# main.net
KiCad netlist of a schematic drawn in Altium Designer
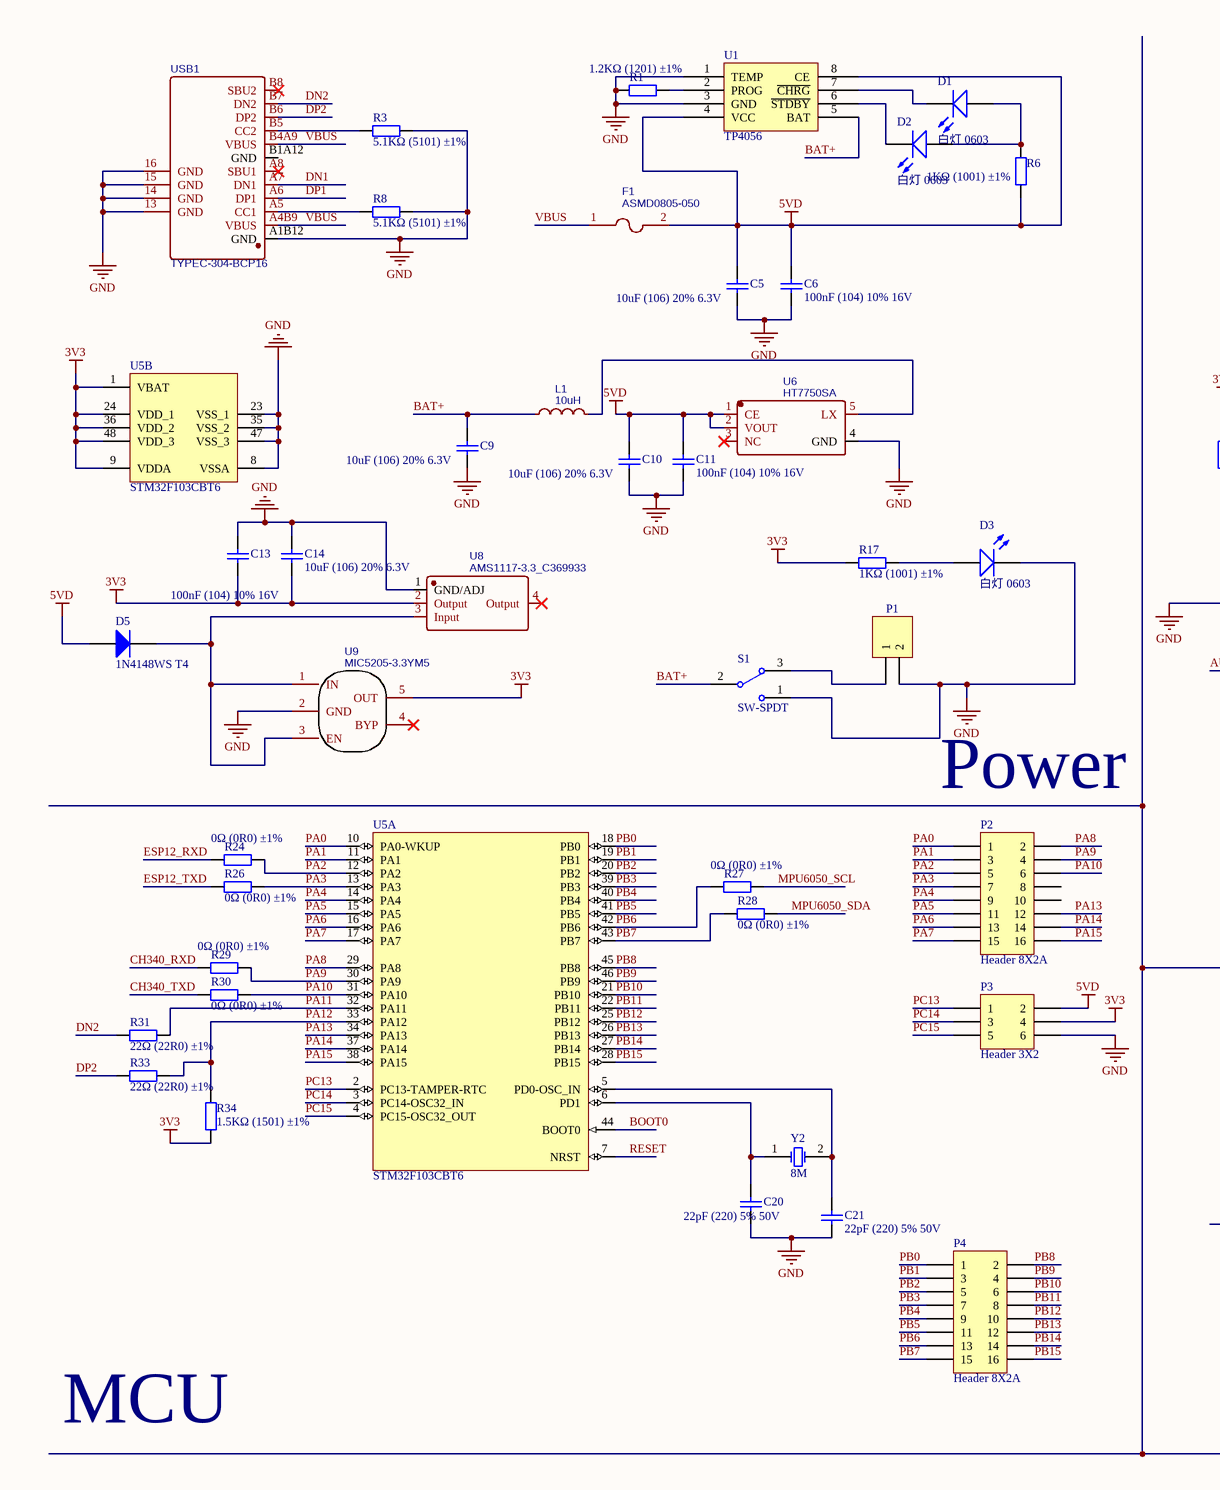
[diagram p0: main.SchDoc, left]
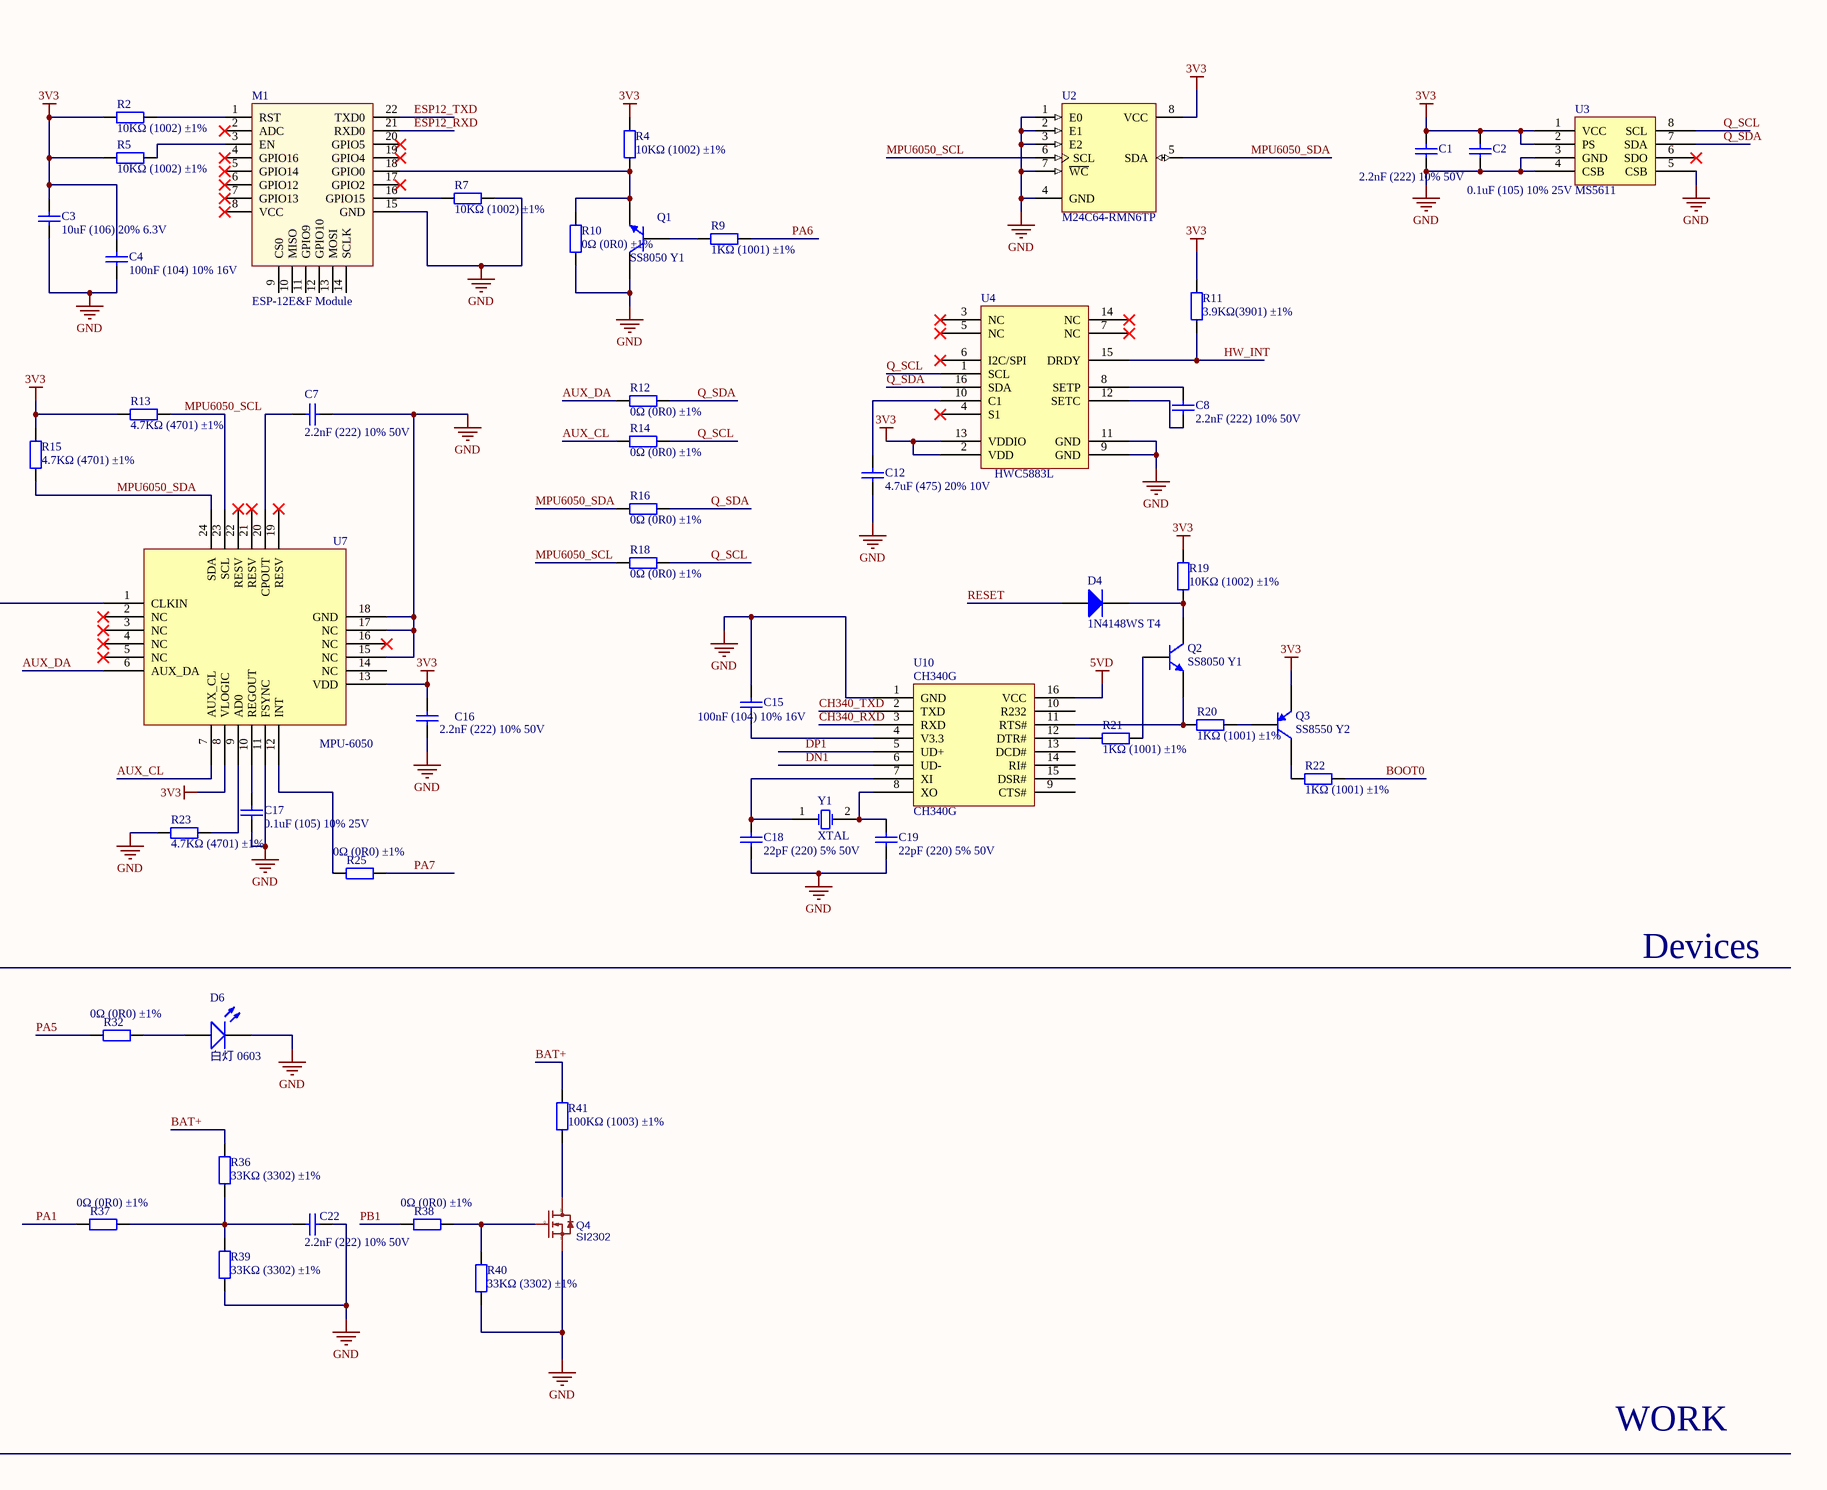
[diagram p1: main.SchDoc, right]

(export (version "E")
  (design (tool "Eeschema 10.0.6"))
  (components
    (comp (ref "C1")
      (value "2.2nF (222) 10% 50V")
      (footprint "0402_C")
      (description "贴片电容")
      (libsource (lib "Miscellaneous Devices LC") (part "0402 2.2nF (222) 10% 50V"))
    )
    (comp (ref "C2")
      (value "0.1uF (105) 10% 25V")
      (footprint "0402_C")
      (description "贴片电容")
      (libsource (lib "Miscellaneous Devices LC") (part "0402 1.0uF (105) 10% 25V"))
    )
    (comp (ref "C3")
      (value "10uF (106) 20% 6.3V")
      (footprint "0402_C")
      (description "贴片电容")
      (libsource (lib "Miscellaneous Devices LC") (part "0402 10uF (106) 20% 6.3V"))
    )
    (comp (ref "C4")
      (value "100nF (104) 10% 16V")
      (footprint "0402_C")
      (description "贴片电容")
      (libsource (lib "Miscellaneous Devices LC") (part "0402 100nF (104) 10% 16V"))
    )
    (comp (ref "C5")
      (value "10uF (106) 20% 6.3V")
      (footprint "0402_C")
      (description "贴片电容")
      (libsource (lib "Miscellaneous Devices LC") (part "0402 10uF (106) 20% 6.3V"))
    )
    (comp (ref "C6")
      (value "100nF (104) 10% 16V")
      (footprint "0402_C")
      (description "贴片电容")
      (libsource (lib "Miscellaneous Devices LC") (part "0402 100nF (104) 10% 16V"))
    )
    (comp (ref "C7")
      (value "2.2nF (222) 10% 50V")
      (footprint "0402_C")
      (description "贴片电容")
      (libsource (lib "Miscellaneous Devices LC") (part "0402 2.2nF (222) 10% 50V"))
    )
    (comp (ref "C8")
      (value "2.2nF (222) 10% 50V")
      (footprint "0402_C")
      (description "贴片电容")
      (libsource (lib "Miscellaneous Devices LC") (part "0402 2.2nF (222) 10% 50V"))
    )
    (comp (ref "C9")
      (value "10uF (106) 20% 6.3V")
      (footprint "0402_C")
      (description "贴片电容")
      (libsource (lib "Miscellaneous Devices LC") (part "0402 10uF (106) 20% 6.3V"))
    )
    (comp (ref "C10")
      (value "10uF (106) 20% 6.3V")
      (footprint "0402_C")
      (description "贴片电容")
      (libsource (lib "Miscellaneous Devices LC") (part "0402 10uF (106) 20% 6.3V"))
    )
    (comp (ref "C11")
      (value "100nF (104) 10% 16V")
      (footprint "0402_C")
      (description "贴片电容")
      (libsource (lib "Miscellaneous Devices LC") (part "0402 100nF (104) 10% 16V"))
    )
    (comp (ref "C12")
      (value "4.7uF (475) 20% 10V")
      (footprint "0402_C")
      (description "贴片电容")
      (libsource (lib "Miscellaneous Devices LC") (part "0402 4.7uF (475) 20% 10V"))
    )
    (comp (ref "C13")
      (value "100nF (104) 10% 16V")
      (footprint "0402_C")
      (description "贴片电容")
      (libsource (lib "Miscellaneous Devices LC") (part "0402 100nF (104) 10% 16V"))
    )
    (comp (ref "C14")
      (value "10uF (106) 20% 6.3V")
      (footprint "0402_C")
      (description "贴片电容")
      (libsource (lib "Miscellaneous Devices LC") (part "0402 10uF (106) 20% 6.3V"))
    )
    (comp (ref "C15")
      (value "100nF (104) 10% 16V")
      (footprint "0402_C")
      (description "贴片电容")
      (libsource (lib "Miscellaneous Devices LC") (part "0402 100nF (104) 10% 16V"))
    )
    (comp (ref "C16")
      (value "2.2nF (222) 10% 50V")
      (footprint "0402_C")
      (description "贴片电容")
      (libsource (lib "Miscellaneous Devices LC") (part "0402 2.2nF (222) 10% 50V"))
    )
    (comp (ref "C17")
      (value "0.1uF (105) 10% 25V")
      (footprint "0402_C")
      (description "贴片电容")
      (libsource (lib "Miscellaneous Devices LC") (part "0402 1.0uF (105) 10% 25V"))
    )
    (comp (ref "C18")
      (value "22pF (220) 5% 50V")
      (footprint "0402_C")
      (description "贴片电容")
      (libsource (lib "Miscellaneous Devices LC") (part "0402 22pF (220) 5% 50V"))
    )
    (comp (ref "C19")
      (value "22pF (220) 5% 50V")
      (footprint "0402_C")
      (description "贴片电容")
      (libsource (lib "Miscellaneous Devices LC") (part "0402 22pF (220) 5% 50V"))
    )
    (comp (ref "C20")
      (value "22pF (220) 5% 50V")
      (footprint "0402_C")
      (description "贴片电容")
      (libsource (lib "Miscellaneous Devices LC") (part "0402 22pF (220) 5% 50V"))
    )
    (comp (ref "C21")
      (value "22pF (220) 5% 50V")
      (footprint "0402_C")
      (description "贴片电容")
      (libsource (lib "Miscellaneous Devices LC") (part "0402 22pF (220) 5% 50V"))
    )
    (comp (ref "C22")
      (value "2.2nF (222) 10% 50V")
      (footprint "0402_C")
      (description "贴片电容")
      (libsource (lib "Miscellaneous Devices LC") (part "0402 2.2nF (222) 10% 50V"))
    )
    (comp (ref "D1")
      (value "白灯 0603")
      (footprint "0603_LED_S1")
      (description "发光二极管")
      (libsource (lib "Miscellaneous Devices LC") (part "0603 白灯"))
    )
    (comp (ref "D2")
      (value "白灯 0603")
      (footprint "0603_LED_S1")
      (description "发光二极管")
      (libsource (lib "Miscellaneous Devices LC") (part "0603 白灯"))
    )
    (comp (ref "D3")
      (value "白灯 0603")
      (footprint "0603_LED_S1")
      (description "发光二极管")
      (libsource (lib "Miscellaneous Devices LC") (part "0603 白灯"))
    )
    (comp (ref "D4")
      (value "1N4148WS T4")
      (footprint "SOD-323_L1.8-W1.3-LS2.5-RD")
      (description "二极管")
      (libsource (lib "Miscellaneous Devices LC") (part "SOD-323 1N4148WS T4"))
    )
    (comp (ref "D5")
      (value "1N4148WS T4")
      (footprint "SOD-323_L1.8-W1.3-LS2.5-RD")
      (description "二极管")
      (libsource (lib "Miscellaneous Devices LC") (part "SOD-323 1N4148WS T4"))
    )
    (comp (ref "D6")
      (value "白灯 0603")
      (footprint "0603_LED_S1")
      (description "发光二极管")
      (libsource (lib "Miscellaneous Devices LC") (part "0603 白灯"))
    )
    (comp (ref "F1")
      (value "ASMD0805-050")
      (footprint "F0805")
      (fields (field (name "BOM_SUPPLIER PART") "C135329") (field (name "CONTRIBUTOR") "LCSC"))
      (libsource (lib "altium-import") (part "root_0_ASMD0805-050_"))
    )
    (comp (ref "L1")
      (value "10uH")
      (footprint "IND-SMD_L3.0-W3.0_SWPA3010S")
      (fields
        (field (name "BOM_MANUFACTURER PART") "SWPA3012S100MT")
        (field (name "BOM_SUPPLIER PART") "C48668")
      )
      (libsource (lib "altium-import") (part "root_0_10uH_"))
    )
    (comp (ref "M1")
      (value "ESP-12E&F Module")
      (footprint "ESP-12E&F Module")
      (libsource (lib "smartclock") (part "ESP-12E&F Module"))
    )
    (comp (ref "P1")
      (value "Header 2")
      (footprint "HDR2X1_A")
      (description "接插件")
      (fields (field (name "PUBLISHER") "Altium Limited"))
      (libsource (lib "Fszhang") (part "Header 2"))
    )
    (comp (ref "P2")
      (value "Header 8X2A")
      (footprint "HDR8X2_A1")
      (description "接插件")
      (fields (field (name "PUBLISHER") "Altium Limited"))
      (libsource (lib "Fszhang") (part "Header 8X2A"))
    )
    (comp (ref "P3")
      (value "Header 3X2")
      (footprint "HDR2X3")
      (description "Header, 3-Pin, Dual row")
      (fields (field (name "PUBLISHER") "Altium Limited"))
      (libsource (lib "Sparks") (part "Header 3X2"))
    )
    (comp (ref "P4")
      (value "Header 8X2A")
      (footprint "HDR8X2_A1")
      (description "接插件")
      (fields (field (name "PUBLISHER") "Altium Limited"))
      (libsource (lib "Fszhang") (part "Header 8X2A"))
    )
    (comp (ref "Q1")
      (value "SS8050 Y1")
      (footprint "SOT-23(SOT-23-3)")
      (description "三极管")
      (libsource (lib "Miscellaneous Devices LC") (part "SOT-23 SS8050 Y1"))
    )
    (comp (ref "Q2")
      (value "SS8050 Y1")
      (footprint "SOT-23(SOT-23-3)")
      (description "三极管")
      (libsource (lib "Miscellaneous Devices LC") (part "SOT-23 SS8050 Y1"))
    )
    (comp (ref "Q3")
      (value "SS8550 Y2")
      (footprint "SOT-23(SOT-23-3)")
      (description "三极管")
      (libsource (lib "Miscellaneous Devices LC") (part "SOT-23 SS8550 Y2"))
    )
    (comp (ref "Q4")
      (value "SI2302")
      (footprint "SOT-23-3_L2.9-W1.3-P1.90-LS2.4-BR")
      (fields (field (name "BOM_SUPPLIER PART") "C181087") (field (name "CONTRIBUTOR") "LCSC"))
      (libsource (lib "altium-import") (part "root_0_SI2302_"))
    )
    (comp (ref "R1")
      (value "1.2KΩ (1201) ±1%")
      (footprint "0402_R")
      (description "贴片电阻")
      (libsource (lib "Miscellaneous Devices LC") (part "0402 1.2KΩ (1201) 1%"))
    )
    (comp (ref "R2")
      (value "10KΩ (1002) ±1%")
      (footprint "0402_R")
      (description "贴片电阻")
      (libsource (lib "Miscellaneous Devices LC") (part "0402 10KΩ (1002) 1%"))
    )
    (comp (ref "R3")
      (value "5.1KΩ (5101) ±1%")
      (footprint "0402_R")
      (description "贴片电阻")
      (libsource (lib "Miscellaneous Devices LC") (part "0402 5.1KΩ (5101) 1%"))
    )
    (comp (ref "R4")
      (value "10KΩ (1002) ±1%")
      (footprint "0402_R")
      (description "贴片电阻")
      (libsource (lib "") (part "0402 10KΩ (1002) 1%_1"))
    )
    (comp (ref "R5")
      (value "10KΩ (1002) ±1%")
      (footprint "0402_R")
      (description "贴片电阻")
      (libsource (lib "Miscellaneous Devices LC") (part "0402 10KΩ (1002) 1%"))
    )
    (comp (ref "R6")
      (value "1KΩ (1001) ±1%")
      (footprint "0402_R")
      (description "贴片电阻")
      (libsource (lib "") (part "0402 1KΩ (1001) 1%_2"))
    )
    (comp (ref "R7")
      (value "10KΩ (1002) ±1%")
      (footprint "0402_R")
      (description "贴片电阻")
      (libsource (lib "Miscellaneous Devices LC") (part "0402 10KΩ (1002) 1%"))
    )
    (comp (ref "R8")
      (value "5.1KΩ (5101) ±1%")
      (footprint "0402_R")
      (description "贴片电阻")
      (libsource (lib "Miscellaneous Devices LC") (part "0402 5.1KΩ (5101) 1%"))
    )
    (comp (ref "R9")
      (value "1KΩ (1001) ±1%")
      (footprint "0402_R")
      (description "贴片电阻")
      (libsource (lib "Miscellaneous Devices LC") (part "0402 1KΩ (1001) 1%"))
    )
    (comp (ref "R10")
      (value "0Ω (0R0) ±1%")
      (footprint "0402_R")
      (description "贴片电阻")
      (libsource (lib "") (part "0402 0Ω (0R0) 1%_1"))
    )
    (comp (ref "R11")
      (value "3.9KΩ(3901) ±1%")
      (footprint "0402_R")
      (description "贴片电阻")
      (libsource (lib "Miscellaneous Devices LC") (part "0402 3.9KΩ(3901) 1%"))
    )
    (comp (ref "R12")
      (value "0Ω (0R0) ±1%")
      (footprint "0402_R")
      (description "贴片电阻")
      (libsource (lib "Miscellaneous Devices LC") (part "0402 0Ω (0R0) 1%"))
    )
    (comp (ref "R13")
      (value "4.7KΩ (4701) ±1%")
      (footprint "0402_R")
      (description "贴片电阻")
      (libsource (lib "Miscellaneous Devices LC") (part "0402 4.7KΩ (4701) 1%"))
    )
    (comp (ref "R14")
      (value "0Ω (0R0) ±1%")
      (footprint "0402_R")
      (description "贴片电阻")
      (libsource (lib "Miscellaneous Devices LC") (part "0402 0Ω (0R0) 1%"))
    )
    (comp (ref "R15")
      (value "4.7KΩ (4701) ±1%")
      (footprint "0402_R")
      (description "贴片电阻")
      (libsource (lib "") (part "0402 4.7KΩ (4701) 1%_2"))
    )
    (comp (ref "R16")
      (value "0Ω (0R0) ±1%")
      (footprint "0402_R")
      (description "贴片电阻")
      (libsource (lib "Miscellaneous Devices LC") (part "0402 0Ω (0R0) 1%"))
    )
    (comp (ref "R17")
      (value "1KΩ (1001) ±1%")
      (footprint "0402_R")
      (description "贴片电阻")
      (libsource (lib "Miscellaneous Devices LC") (part "0402 1KΩ (1001) 1%"))
    )
    (comp (ref "R18")
      (value "0Ω (0R0) ±1%")
      (footprint "0402_R")
      (description "贴片电阻")
      (libsource (lib "Miscellaneous Devices LC") (part "0402 0Ω (0R0) 1%"))
    )
    (comp (ref "R19")
      (value "10KΩ (1002) ±1%")
      (footprint "0402_R")
      (description "贴片电阻")
      (libsource (lib "") (part "0402 10KΩ (1002) 1%_1"))
    )
    (comp (ref "R20")
      (value "1KΩ (1001) ±1%")
      (footprint "0402_R")
      (description "贴片电阻")
      (libsource (lib "Miscellaneous Devices LC") (part "0402 1KΩ (1001) 1%"))
    )
    (comp (ref "R21")
      (value "1KΩ (1001) ±1%")
      (footprint "0402_R")
      (description "贴片电阻")
      (libsource (lib "Miscellaneous Devices LC") (part "0402 1KΩ (1001) 1%"))
    )
    (comp (ref "R22")
      (value "1KΩ (1001) ±1%")
      (footprint "0402_R")
      (description "贴片电阻")
      (libsource (lib "") (part "0402 1KΩ (1001) 1%_1"))
    )
    (comp (ref "R23")
      (value "4.7KΩ (4701) ±1%")
      (footprint "0402_R")
      (description "贴片电阻")
      (libsource (lib "") (part "0402 4.7KΩ (4701) 1%_1"))
    )
    (comp (ref "R24")
      (value "0Ω (0R0) ±1%")
      (footprint "0402_R")
      (description "贴片电阻")
      (libsource (lib "Miscellaneous Devices LC") (part "0402 0Ω (0R0) 1%"))
    )
    (comp (ref "R25")
      (value "0Ω (0R0) ±1%")
      (footprint "0402_R")
      (description "贴片电阻")
      (libsource (lib "Miscellaneous Devices LC") (part "0402 0Ω (0R0) 1%"))
    )
    (comp (ref "R26")
      (value "0Ω (0R0) ±1%")
      (footprint "0402_R")
      (description "贴片电阻")
      (libsource (lib "Miscellaneous Devices LC") (part "0402 0Ω (0R0) 1%"))
    )
    (comp (ref "R27")
      (value "0Ω (0R0) ±1%")
      (footprint "0402_R")
      (description "贴片电阻")
      (libsource (lib "Miscellaneous Devices LC") (part "0402 0Ω (0R0) 1%"))
    )
    (comp (ref "R28")
      (value "0Ω (0R0) ±1%")
      (footprint "0402_R")
      (description "贴片电阻")
      (libsource (lib "Miscellaneous Devices LC") (part "0402 0Ω (0R0) 1%"))
    )
    (comp (ref "R29")
      (value "0Ω (0R0) ±1%")
      (footprint "0402_R")
      (description "贴片电阻")
      (libsource (lib "Miscellaneous Devices LC") (part "0402 0Ω (0R0) 1%"))
    )
    (comp (ref "R30")
      (value "0Ω (0R0) ±1%")
      (footprint "0402_R")
      (description "贴片电阻")
      (libsource (lib "Miscellaneous Devices LC") (part "0402 0Ω (0R0) 1%"))
    )
    (comp (ref "R31")
      (value "22Ω (22R0) ±1%")
      (footprint "0402_R")
      (description "贴片电阻")
      (libsource (lib "Miscellaneous Devices LC") (part "0402 22Ω (22R0) 1%"))
    )
    (comp (ref "R32")
      (value "0Ω (0R0) ±1%")
      (footprint "0402_R")
      (description "贴片电阻")
      (libsource (lib "Miscellaneous Devices LC") (part "0402 0Ω (0R0) 1%"))
    )
    (comp (ref "R33")
      (value "22Ω (22R0) ±1%")
      (footprint "0402_R")
      (description "贴片电阻")
      (libsource (lib "Miscellaneous Devices LC") (part "0402 22Ω (22R0) 1%"))
    )
    (comp (ref "R34")
      (value "1.5KΩ (1501) ±1%")
      (footprint "0402_R")
      (description "贴片电阻")
      (libsource (lib "Miscellaneous Devices LC") (part "0402 1.5KΩ (1501) 1%"))
    )
    (comp (ref "R36")
      (value "33KΩ (3302) ±1%")
      (footprint "0402_R")
      (description "贴片电阻")
      (libsource (lib "Miscellaneous Devices LC") (part "0402 33KΩ (3302) 1%"))
    )
    (comp (ref "R37")
      (value "0Ω (0R0) ±1%")
      (footprint "0402_R")
      (description "贴片电阻")
      (libsource (lib "Miscellaneous Devices LC") (part "0402 0Ω (0R0) 1%"))
    )
    (comp (ref "R38")
      (value "0Ω (0R0) ±1%")
      (footprint "0402_R")
      (description "贴片电阻")
      (libsource (lib "Miscellaneous Devices LC") (part "0402 0Ω (0R0) 1%"))
    )
    (comp (ref "R39")
      (value "33KΩ (3302) ±1%")
      (footprint "0402_R")
      (description "贴片电阻")
      (libsource (lib "Miscellaneous Devices LC") (part "0402 33KΩ (3302) 1%"))
    )
    (comp (ref "R40")
      (value "33KΩ (3302) ±1%")
      (footprint "0402_R")
      (description "贴片电阻")
      (libsource (lib "Miscellaneous Devices LC") (part "0402 33KΩ (3302) 1%"))
    )
    (comp (ref "R41")
      (value "100KΩ (1003) ±1%")
      (footprint "0805_R")
      (description "贴片电阻")
      (libsource (lib "Miscellaneous Devices LC") (part "0805 100KΩ (1003) 1%"))
    )
    (comp (ref "S1")
      (value "SW-SPDT")
      (footprint "SWITCH_A1")
      (description "开关")
      (fields (field (name "PUBLISHER") "Altium Limited"))
      (libsource (lib "Fszhang") (part "SW-SPDT"))
    )
    (comp (ref "U1")
      (value "TP4056")
      (footprint "SOP-8_EP_150mil")
      (description "电池电源管理")
      (libsource (lib "Miscellaneous Devices LC") (part "TP4056_[C16581]"))
    )
    (comp (ref "U2")
      (value "M24C64-RMN6TP")
      (footprint "SOIC-8_150mil")
      (description "EEPROM")
      (libsource (lib "Miscellaneous Devices LC") (part "M24C64-RMN6TP"))
    )
    (comp (ref "U3")
      (value "MS5611")
      (footprint "MS5611 - duplicate")
      (libsource (lib "aircraftschlib") (part "MS5611"))
    )
    (comp (ref "U4")
      (value "HWC5883L")
      (footprint "LPCC-16_L3.0-W3.0-P0.50-BL")
      (libsource (lib "aircraftschlib") (part "HMC5883L"))
    )
    (comp (ref "U5")
      (value "STM32F103CBT6")
      (footprint "LQFP-48_7x7x05P")
      (description "ARM")
      (libsource (lib "Miscellaneous Devices LC") (part "STM32F103CBT6"))
    )
    (comp (ref "U6")
      (value "HT7750SA")
      (footprint "SOT-23-5")
      (fields (field (name "BOM_SUPPLIER PART") "C192571") (field (name "CONTRIBUTOR") "LCSC"))
      (libsource (lib "altium-import") (part "root_0_HT7750SA_"))
    )
    (comp (ref "U7")
      (value "MPU-6050")
      (footprint "QFN-24_4x4x05P")
      (description "传感器")
      (libsource (lib "Miscellaneous Devices LC") (part "MPU-6050"))
    )
    (comp (ref "U8")
      (value "AMS1117-3.3_C369933")
      (footprint "SOT-223-3_L6.5-W3.4-P2.30-LS7.0-BR")
      (fields
        (field (name "BOM_SUPPLIER PART") "C369933")
        (field (name "BOM_MANUFACTURER PART") "AMS1117-3.3")
        (field (name "CONTRIBUTOR") "LCSC")
      )
      (libsource (lib "altium-import") (part "root_0_AMS1117-3.3_C369933_"))
    )
    (comp (ref "U9")
      (value "MIC5205-3.3YM5")
      (footprint "SOT-23-5")
      (fields (field (name "BOM_SUPPLIER PART") "C37970"))
      (libsource (lib "altium-import") (part "root_0_MIC5205-3.3YM5_"))
    )
    (comp (ref "U10")
      (value "CH340G")
      (footprint "SOIC-16_L9.9-W3.9-P1.27-LS6.0-BR")
      (description "USB")
      (libsource (lib "Miscellaneous Devices LC") (part "CH340G"))
    )
    (comp (ref "USB1")
      (value "TYPEC-304-BCP16")
      (footprint "USB-C-SMD_TYPEC-304-BCP16")
      (fields (field (name "BOM_SUPPLIER PART") "C720629") (field (name "CONTRIBUTOR") "LCSC"))
      (libsource (lib "altium-import") (part "root_2_TYPEC-304-BCP16_"))
    )
    (comp (ref "Y1")
      (value "XTAL")
      (footprint "XTAL_socket")
      (description "Crystal Oscillator")
      (fields (field (name "PUBLISHER") "Altium Limited"))
      (libsource (lib "Miscellaneous Devices") (part "XTAL"))
    )
    (comp (ref "Y2")
      (value "8M")
      (footprint "XTAL_socket")
      (description "Crystal Oscillator")
      (fields (field (name "PUBLISHER") "Altium Limited"))
      (libsource (lib "Miscellaneous Devices") (part "XTAL"))
    )
  )
  (nets
    (net (code "1") (name "/AUX_CL") (class "Default")
      (node (ref "R14") (pin "1") (pinfunction "1_1") (pintype "passive"))
      (node (ref "U7") (pin "7") (pinfunction "AUX_CL_7") (pintype "passive"))
    )
    (net (code "2") (name "/AUX_DA") (class "Default")
      (node (ref "R12") (pin "1") (pinfunction "1_1") (pintype "passive"))
      (node (ref "U7") (pin "6") (pinfunction "AUX_DA_6") (pintype "passive"))
    )
    (net (code "3") (name "/BAT+") (class "Default")
      (node (ref "C9") (pin "2") (pinfunction "2_2") (pintype "passive"))
      (node (ref "L1") (pin "1") (pinfunction "1_1") (pintype "passive"))
      (node (ref "R36") (pin "2") (pinfunction "2_2") (pintype "passive"))
      (node (ref "R41") (pin "2") (pinfunction "2_2") (pintype "passive"))
      (node (ref "S1") (pin "2") (pinfunction "2_2") (pintype "passive"))
      (node (ref "U1") (pin "5") (pinfunction "BAT_5") (pintype "passive"))
    )
    (net (code "4") (name "/BOOT0") (class "Default")
      (node (ref "R22") (pin "1") (pinfunction "1_1") (pintype "passive"))
      (node (ref "U5") (pin "44") (pinfunction "BOOT0_44") (pintype "input"))
    )
    (net (code "5") (name "/CH340_RXD") (class "Default")
      (node (ref "R29") (pin "1") (pinfunction "1_1") (pintype "passive"))
      (node (ref "U10") (pin "3") (pinfunction "RXD_3") (pintype "passive"))
    )
    (net (code "6") (name "/CH340_TXD") (class "Default")
      (node (ref "R30") (pin "1") (pinfunction "1_1") (pintype "passive"))
      (node (ref "U10") (pin "2") (pinfunction "TXD_2") (pintype "passive"))
    )
    (net (code "7") (name "/DN1") (class "Default")
      (node (ref "U10") (pin "6") (pinfunction "UD-_6") (pintype "passive"))
      (node (ref "USB1") (pin "A7") (pinfunction "DN1_A7") (pintype "passive"))
    )
    (net (code "8") (name "/DN2") (class "Default")
      (node (ref "R31") (pin "1") (pinfunction "1_1") (pintype "passive"))
      (node (ref "USB1") (pin "B7") (pinfunction "DN2_B7") (pintype "passive"))
    )
    (net (code "9") (name "/DP1") (class "Default")
      (node (ref "U10") (pin "5") (pinfunction "UD+_5") (pintype "passive"))
      (node (ref "USB1") (pin "A6") (pinfunction "DP1_A6") (pintype "passive"))
    )
    (net (code "10") (name "/DP2") (class "Default")
      (node (ref "R33") (pin "1") (pinfunction "1_1") (pintype "passive"))
      (node (ref "USB1") (pin "B6") (pinfunction "DP2_B6") (pintype "passive"))
    )
    (net (code "11") (name "/ESP12_RXD") (class "Default")
      (node (ref "M1") (pin "21") (pinfunction "RXD0_21") (pintype "passive"))
      (node (ref "R24") (pin "1") (pinfunction "1_1") (pintype "passive"))
    )
    (net (code "12") (name "/ESP12_TXD") (class "Default")
      (node (ref "M1") (pin "22") (pinfunction "TXD0_22") (pintype "passive"))
      (node (ref "R26") (pin "1") (pinfunction "1_1") (pintype "passive"))
    )
    (net (code "13") (name "/HW_INT") (class "Default")
      (node (ref "R11") (pin "1") (pinfunction "1_1") (pintype "passive"))
      (node (ref "U4") (pin "15") (pinfunction "DRDY_15") (pintype "passive"))
    )
    (net (code "14") (name "/MPU6050_SCL") (class "Default")
      (node (ref "R13") (pin "2") (pinfunction "2_2") (pintype "passive"))
      (node (ref "R18") (pin "1") (pinfunction "1_1") (pintype "passive"))
      (node (ref "R27") (pin "2") (pinfunction "2_2") (pintype "passive"))
      (node (ref "U2") (pin "6") (pinfunction "SCL_6") (pintype "input"))
      (node (ref "U7") (pin "23") (pinfunction "SCL_23") (pintype "passive"))
    )
    (net (code "15") (name "/MPU6050_SDA") (class "Default")
      (node (ref "R15") (pin "1") (pinfunction "1_1") (pintype "passive"))
      (node (ref "R16") (pin "1") (pinfunction "1_1") (pintype "passive"))
      (node (ref "R28") (pin "2") (pinfunction "2_2") (pintype "passive"))
      (node (ref "U2") (pin "5") (pinfunction "SDA_5") (pintype "bidirectional"))
      (node (ref "U7") (pin "24") (pinfunction "SDA_24") (pintype "passive"))
    )
    (net (code "16") (name "/PA0") (class "Default")
      (node (ref "P2") (pin "1") (pinfunction "1_1") (pintype "passive"))
      (node (ref "U5") (pin "10") (pinfunction "PA0-WKUP_10") (pintype "bidirectional"))
    )
    (net (code "17") (name "/PA1") (class "Default")
      (node (ref "P2") (pin "3") (pinfunction "3_3") (pintype "passive"))
      (node (ref "R37") (pin "1") (pinfunction "1_1") (pintype "passive"))
      (node (ref "U5") (pin "11") (pinfunction "PA1_11") (pintype "bidirectional"))
    )
    (net (code "18") (name "/PA2") (class "Default")
      (node (ref "P2") (pin "5") (pinfunction "5_5") (pintype "passive"))
      (node (ref "R24") (pin "2") (pinfunction "2_2") (pintype "passive"))
      (node (ref "U5") (pin "12") (pinfunction "PA2_12") (pintype "bidirectional"))
    )
    (net (code "19") (name "/PA3") (class "Default")
      (node (ref "P2") (pin "7") (pinfunction "7_7") (pintype "passive"))
      (node (ref "R26") (pin "2") (pinfunction "2_2") (pintype "passive"))
      (node (ref "U5") (pin "13") (pinfunction "PA3_13") (pintype "bidirectional"))
    )
    (net (code "20") (name "/PA4") (class "Default")
      (node (ref "P2") (pin "9") (pinfunction "9_9") (pintype "passive"))
      (node (ref "U5") (pin "14") (pinfunction "PA4_14") (pintype "bidirectional"))
    )
    (net (code "21") (name "/PA5") (class "Default")
      (node (ref "P2") (pin "11") (pinfunction "11_11") (pintype "passive"))
      (node (ref "R32") (pin "1") (pinfunction "1_1") (pintype "passive"))
      (node (ref "U5") (pin "15") (pinfunction "PA5_15") (pintype "bidirectional"))
    )
    (net (code "22") (name "/PA6") (class "Default")
      (node (ref "P2") (pin "13") (pinfunction "13_13") (pintype "passive"))
      (node (ref "R9") (pin "2") (pinfunction "2_2") (pintype "passive"))
      (node (ref "U5") (pin "16") (pinfunction "PA6_16") (pintype "bidirectional"))
    )
    (net (code "23") (name "/PA7") (class "Default")
      (node (ref "P2") (pin "15") (pinfunction "15_15") (pintype "passive"))
      (node (ref "R25") (pin "2") (pinfunction "2_2") (pintype "passive"))
      (node (ref "U5") (pin "17") (pinfunction "PA7_17") (pintype "bidirectional"))
    )
    (net (code "24") (name "/PA8") (class "Default")
      (node (ref "P2") (pin "2") (pinfunction "2_2") (pintype "passive"))
      (node (ref "U5") (pin "29") (pinfunction "PA8_29") (pintype "bidirectional"))
    )
    (net (code "25") (name "/PA9") (class "Default")
      (node (ref "P2") (pin "4") (pinfunction "4_4") (pintype "passive"))
      (node (ref "R29") (pin "2") (pinfunction "2_2") (pintype "passive"))
      (node (ref "U5") (pin "30") (pinfunction "PA9_30") (pintype "bidirectional"))
    )
    (net (code "26") (name "/PA10") (class "Default")
      (node (ref "P2") (pin "6") (pinfunction "6_6") (pintype "passive"))
      (node (ref "R30") (pin "2") (pinfunction "2_2") (pintype "passive"))
      (node (ref "U5") (pin "31") (pinfunction "PA10_31") (pintype "bidirectional"))
    )
    (net (code "27") (name "/PA11") (class "Default")
      (node (ref "R31") (pin "2") (pinfunction "2_2") (pintype "passive"))
      (node (ref "U5") (pin "32") (pinfunction "PA11_32") (pintype "bidirectional"))
    )
    (net (code "28") (name "/PA12") (class "Default")
      (node (ref "R33") (pin "2") (pinfunction "2_2") (pintype "passive"))
      (node (ref "R34") (pin "2") (pinfunction "2_2") (pintype "passive"))
      (node (ref "U5") (pin "33") (pinfunction "PA12_33") (pintype "bidirectional"))
    )
    (net (code "29") (name "/PA13") (class "Default")
      (node (ref "P2") (pin "12") (pinfunction "12_12") (pintype "passive"))
      (node (ref "U5") (pin "34") (pinfunction "PA13_34") (pintype "bidirectional"))
    )
    (net (code "30") (name "/PA14") (class "Default")
      (node (ref "P2") (pin "14") (pinfunction "14_14") (pintype "passive"))
      (node (ref "U5") (pin "37") (pinfunction "PA14_37") (pintype "bidirectional"))
    )
    (net (code "31") (name "/PA15") (class "Default")
      (node (ref "P2") (pin "16") (pinfunction "16_16") (pintype "passive"))
      (node (ref "U5") (pin "38") (pinfunction "PA15_38") (pintype "bidirectional"))
    )
    (net (code "32") (name "/PB0") (class "Default")
      (node (ref "P4") (pin "1") (pinfunction "1_1") (pintype "passive"))
      (node (ref "U5") (pin "18") (pinfunction "PB0_18") (pintype "bidirectional"))
    )
    (net (code "33") (name "/PB1") (class "Default")
      (node (ref "P4") (pin "3") (pinfunction "3_3") (pintype "passive"))
      (node (ref "R38") (pin "1") (pinfunction "1_1") (pintype "passive"))
      (node (ref "U5") (pin "19") (pinfunction "PB1_19") (pintype "bidirectional"))
    )
    (net (code "34") (name "/PB2") (class "Default")
      (node (ref "P4") (pin "5") (pinfunction "5_5") (pintype "passive"))
      (node (ref "U5") (pin "20") (pinfunction "PB2_20") (pintype "bidirectional"))
    )
    (net (code "35") (name "/PB3") (class "Default")
      (node (ref "P4") (pin "7") (pinfunction "7_7") (pintype "passive"))
      (node (ref "U5") (pin "39") (pinfunction "PB3_39") (pintype "bidirectional"))
    )
    (net (code "36") (name "/PB4") (class "Default")
      (node (ref "P4") (pin "9") (pinfunction "9_9") (pintype "passive"))
      (node (ref "U5") (pin "40") (pinfunction "PB4_40") (pintype "bidirectional"))
    )
    (net (code "37") (name "/PB5") (class "Default")
      (node (ref "P4") (pin "11") (pinfunction "11_11") (pintype "passive"))
      (node (ref "U5") (pin "41") (pinfunction "PB5_41") (pintype "bidirectional"))
    )
    (net (code "38") (name "/PB6") (class "Default")
      (node (ref "P4") (pin "13") (pinfunction "13_13") (pintype "passive"))
      (node (ref "R27") (pin "1") (pinfunction "1_1") (pintype "passive"))
      (node (ref "U5") (pin "42") (pinfunction "PB6_42") (pintype "bidirectional"))
    )
    (net (code "39") (name "/PB7") (class "Default")
      (node (ref "P4") (pin "15") (pinfunction "15_15") (pintype "passive"))
      (node (ref "R28") (pin "1") (pinfunction "1_1") (pintype "passive"))
      (node (ref "U5") (pin "43") (pinfunction "PB7_43") (pintype "bidirectional"))
    )
    (net (code "40") (name "/PB8") (class "Default")
      (node (ref "P4") (pin "2") (pinfunction "2_2") (pintype "passive"))
      (node (ref "U5") (pin "45") (pinfunction "PB8_45") (pintype "bidirectional"))
    )
    (net (code "41") (name "/PB9") (class "Default")
      (node (ref "P4") (pin "4") (pinfunction "4_4") (pintype "passive"))
      (node (ref "U5") (pin "46") (pinfunction "PB9_46") (pintype "bidirectional"))
    )
    (net (code "42") (name "/PB10") (class "Default")
      (node (ref "P4") (pin "6") (pinfunction "6_6") (pintype "passive"))
      (node (ref "U5") (pin "21") (pinfunction "PB10_21") (pintype "bidirectional"))
    )
    (net (code "43") (name "/PB11") (class "Default")
      (node (ref "P4") (pin "8") (pinfunction "8_8") (pintype "passive"))
      (node (ref "U5") (pin "22") (pinfunction "PB11_22") (pintype "bidirectional"))
    )
    (net (code "44") (name "/PB12") (class "Default")
      (node (ref "P4") (pin "10") (pinfunction "10_10") (pintype "passive"))
      (node (ref "U5") (pin "25") (pinfunction "PB12_25") (pintype "bidirectional"))
    )
    (net (code "45") (name "/PB13") (class "Default")
      (node (ref "P4") (pin "12") (pinfunction "12_12") (pintype "passive"))
      (node (ref "U5") (pin "26") (pinfunction "PB13_26") (pintype "bidirectional"))
    )
    (net (code "46") (name "/PB14") (class "Default")
      (node (ref "P4") (pin "14") (pinfunction "14_14") (pintype "passive"))
      (node (ref "U5") (pin "27") (pinfunction "PB14_27") (pintype "bidirectional"))
    )
    (net (code "47") (name "/PB15") (class "Default")
      (node (ref "P4") (pin "16") (pinfunction "16_16") (pintype "passive"))
      (node (ref "U5") (pin "28") (pinfunction "PB15_28") (pintype "bidirectional"))
    )
    (net (code "48") (name "/PC13") (class "Default")
      (node (ref "P3") (pin "1") (pinfunction "1_1") (pintype "passive"))
      (node (ref "U5") (pin "2") (pinfunction "PC13-TAMPER-RTC_2") (pintype "bidirectional"))
    )
    (net (code "49") (name "/PC14") (class "Default")
      (node (ref "P3") (pin "3") (pinfunction "3_3") (pintype "passive"))
      (node (ref "U5") (pin "3") (pinfunction "PC14-OSC32_IN_3") (pintype "bidirectional"))
    )
    (net (code "50") (name "/PC15") (class "Default")
      (node (ref "P3") (pin "5") (pinfunction "5_5") (pintype "passive"))
      (node (ref "U5") (pin "4") (pinfunction "PC15-OSC32_OUT_4") (pintype "bidirectional"))
    )
    (net (code "51") (name "/Q_SCL") (class "Default")
      (node (ref "R14") (pin "2") (pinfunction "2_2") (pintype "passive"))
      (node (ref "R18") (pin "2") (pinfunction "2_2") (pintype "passive"))
      (node (ref "U3") (pin "8") (pinfunction "SCL_8") (pintype "passive"))
      (node (ref "U4") (pin "1") (pinfunction "SCL_1") (pintype "passive"))
    )
    (net (code "52") (name "/Q_SDA") (class "Default")
      (node (ref "R12") (pin "2") (pinfunction "2_2") (pintype "passive"))
      (node (ref "R16") (pin "2") (pinfunction "2_2") (pintype "passive"))
      (node (ref "U3") (pin "7") (pinfunction "SDA_7") (pintype "passive"))
      (node (ref "U4") (pin "16") (pinfunction "SDA_16") (pintype "passive"))
    )
    (net (code "53") (name "/RESET") (class "Default")
      (node (ref "D4") (pin "1") (pinfunction "A_1") (pintype "passive"))
      (node (ref "U5") (pin "7") (pinfunction "NRST_7") (pintype "bidirectional"))
    )
    (net (code "54") (name "/VBUS") (class "Default")
      (node (ref "F1") (pin "1") (pinfunction "1_1") (pintype "passive"))
      (node (ref "USB1") (pin "A4B9") (pinfunction "VBUS_A4B9") (pintype "passive"))
      (node (ref "USB1") (pin "B4A9") (pinfunction "VBUS_B4A9") (pintype "passive"))
    )
    (net (code "55") (name "3V3") (class "Default")
      (node (ref "C1") (pin "2") (pinfunction "2_2") (pintype "passive"))
      (node (ref "C13") (pin "1") (pinfunction "1_1") (pintype "passive"))
      (node (ref "C14") (pin "1") (pinfunction "1_1") (pintype "passive"))
      (node (ref "C16") (pin "2") (pinfunction "2_2") (pintype "passive"))
      (node (ref "C2") (pin "2") (pinfunction "2_2") (pintype "passive"))
      (node (ref "C3") (pin "2") (pinfunction "2_2") (pintype "passive"))
      (node (ref "C4") (pin "2") (pinfunction "2_2") (pintype "passive"))
      (node (ref "P3") (pin "4") (pinfunction "4_4") (pintype "passive"))
      (node (ref "Q3") (pin "2") (pinfunction "E_2") (pintype "passive"))
      (node (ref "R11") (pin "2") (pinfunction "2_2") (pintype "passive"))
      (node (ref "R13") (pin "1") (pinfunction "1_1") (pintype "passive"))
      (node (ref "R15") (pin "2") (pinfunction "2_2") (pintype "passive"))
      (node (ref "R17") (pin "1") (pinfunction "1_1") (pintype "passive"))
      (node (ref "R19") (pin "2") (pinfunction "2_2") (pintype "passive"))
      (node (ref "R2") (pin "1") (pinfunction "1_1") (pintype "passive"))
      (node (ref "R34") (pin "1") (pinfunction "1_1") (pintype "passive"))
      (node (ref "R4") (pin "2") (pinfunction "2_2") (pintype "passive"))
      (node (ref "R5") (pin "1") (pinfunction "1_1") (pintype "passive"))
      (node (ref "U2") (pin "8") (pinfunction "VCC_8") (pintype "power_in"))
      (node (ref "U3") (pin "1") (pinfunction "VCC_1") (pintype "passive"))
      (node (ref "U3") (pin "2") (pinfunction "PS_2") (pintype "passive"))
      (node (ref "U4") (pin "13") (pinfunction "VDDIO_13") (pintype "passive"))
      (node (ref "U4") (pin "2") (pinfunction "VDD_2") (pintype "passive"))
      (node (ref "U5") (pin "1") (pinfunction "VBAT_1") (pintype "power_in"))
      (node (ref "U5") (pin "24") (pinfunction "VDD_1_24") (pintype "power_in"))
      (node (ref "U5") (pin "36") (pinfunction "VDD_2_36") (pintype "power_in"))
      (node (ref "U5") (pin "48") (pinfunction "VDD_3_48") (pintype "power_in"))
      (node (ref "U5") (pin "9") (pinfunction "VDDA_9") (pintype "power_in"))
      (node (ref "U7") (pin "13") (pinfunction "VDD_13") (pintype "passive"))
      (node (ref "U7") (pin "8") (pinfunction "VLOGIC_8") (pintype "passive"))
      (node (ref "U8") (pin "2") (pinfunction "Output_2") (pintype "passive"))
      (node (ref "U9") (pin "5") (pinfunction "OUT_5") (pintype "passive"))
    )
    (net (code "56") (name "5VD") (class "Default")
      (node (ref "C10") (pin "2") (pinfunction "2_2") (pintype "passive"))
      (node (ref "C11") (pin "2") (pinfunction "2_2") (pintype "passive"))
      (node (ref "C5") (pin "2") (pinfunction "2_2") (pintype "passive"))
      (node (ref "C6") (pin "2") (pinfunction "2_2") (pintype "passive"))
      (node (ref "D5") (pin "1") (pinfunction "A_1") (pintype "passive"))
      (node (ref "F1") (pin "2") (pinfunction "2_2") (pintype "passive"))
      (node (ref "P3") (pin "2") (pinfunction "2_2") (pintype "passive"))
      (node (ref "R6") (pin "1") (pinfunction "1_1") (pintype "passive"))
      (node (ref "U1") (pin "4") (pinfunction "VCC_4") (pintype "passive"))
      (node (ref "U1") (pin "8") (pinfunction "CE_8") (pintype "passive"))
      (node (ref "U10") (pin "16") (pinfunction "VCC_16") (pintype "passive"))
      (node (ref "U6") (pin "1") (pinfunction "CE_1") (pintype "passive"))
      (node (ref "U6") (pin "2") (pinfunction "VOUT_2") (pintype "passive"))
    )
    (net (code "57") (name "GND") (class "Default")
      (node (ref "C1") (pin "1") (pinfunction "1_1") (pintype "passive"))
      (node (ref "C10") (pin "1") (pinfunction "1_1") (pintype "passive"))
      (node (ref "C11") (pin "1") (pinfunction "1_1") (pintype "passive"))
      (node (ref "C12") (pin "1") (pinfunction "1_1") (pintype "passive"))
      (node (ref "C13") (pin "2") (pinfunction "2_2") (pintype "passive"))
      (node (ref "C14") (pin "2") (pinfunction "2_2") (pintype "passive"))
      (node (ref "C15") (pin "2") (pinfunction "2_2") (pintype "passive"))
      (node (ref "C16") (pin "1") (pinfunction "1_1") (pintype "passive"))
      (node (ref "C17") (pin "1") (pinfunction "1_1") (pintype "passive"))
      (node (ref "C18") (pin "1") (pinfunction "1_1") (pintype "passive"))
      (node (ref "C19") (pin "1") (pinfunction "1_1") (pintype "passive"))
      (node (ref "C2") (pin "1") (pinfunction "1_1") (pintype "passive"))
      (node (ref "C20") (pin "1") (pinfunction "1_1") (pintype "passive"))
      (node (ref "C21") (pin "1") (pinfunction "1_1") (pintype "passive"))
      (node (ref "C22") (pin "2") (pinfunction "2_2") (pintype "passive"))
      (node (ref "C3") (pin "1") (pinfunction "1_1") (pintype "passive"))
      (node (ref "C4") (pin "1") (pinfunction "1_1") (pintype "passive"))
      (node (ref "C5") (pin "1") (pinfunction "1_1") (pintype "passive"))
      (node (ref "C6") (pin "1") (pinfunction "1_1") (pintype "passive"))
      (node (ref "C7") (pin "2") (pinfunction "2_2") (pintype "passive"))
      (node (ref "C9") (pin "1") (pinfunction "1_1") (pintype "passive"))
      (node (ref "D3") (pin "K") (pinfunction "K_K") (pintype "passive"))
      (node (ref "D6") (pin "K") (pinfunction "K_K") (pintype "passive"))
      (node (ref "M1") (pin "15") (pinfunction "GND_15") (pintype "passive"))
      (node (ref "P1") (pin "2") (pinfunction "2_2") (pintype "passive"))
      (node (ref "P3") (pin "6") (pinfunction "6_6") (pintype "passive"))
      (node (ref "Q1") (pin "3") (pinfunction "C_3") (pintype "passive"))
      (node (ref "Q4") (pin "2") (pinfunction "S_2") (pintype "passive"))
      (node (ref "R1") (pin "1") (pinfunction "1_1") (pintype "passive"))
      (node (ref "R10") (pin "1") (pinfunction "1_1") (pintype "passive"))
      (node (ref "R23") (pin "2") (pinfunction "2_2") (pintype "passive"))
      (node (ref "R3") (pin "1") (pinfunction "1_1") (pintype "passive"))
      (node (ref "R39") (pin "1") (pinfunction "1_1") (pintype "passive"))
      (node (ref "R40") (pin "1") (pinfunction "1_1") (pintype "passive"))
      (node (ref "R7") (pin "2") (pinfunction "2_2") (pintype "passive"))
      (node (ref "R8") (pin "1") (pinfunction "1_1") (pintype "passive"))
      (node (ref "S1") (pin "1") (pinfunction "1_1") (pintype "passive"))
      (node (ref "U1") (pin "1") (pinfunction "TEMP_1") (pintype "passive"))
      (node (ref "U1") (pin "3") (pinfunction "GND_3") (pintype "passive"))
      (node (ref "U10") (pin "1") (pinfunction "GND_1") (pintype "passive"))
      (node (ref "U2") (pin "1") (pinfunction "E0_1") (pintype "input"))
      (node (ref "U2") (pin "2") (pinfunction "E1_2") (pintype "input"))
      (node (ref "U2") (pin "3") (pinfunction "E2_3") (pintype "input"))
      (node (ref "U2") (pin "4") (pinfunction "GND_4") (pintype "power_in"))
      (node (ref "U2") (pin "7") (pinfunction "~{WC}_7") (pintype "input"))
      (node (ref "U3") (pin "3") (pinfunction "GND_3") (pintype "passive"))
      (node (ref "U3") (pin "4") (pinfunction "CSB_4") (pintype "passive"))
      (node (ref "U3") (pin "5") (pinfunction "CSB_5") (pintype "passive"))
      (node (ref "U4") (pin "11") (pinfunction "GND_11") (pintype "passive"))
      (node (ref "U4") (pin "9") (pinfunction "GND_9") (pintype "passive"))
      (node (ref "U5") (pin "23") (pinfunction "VSS_1_23") (pintype "power_in"))
      (node (ref "U5") (pin "35") (pinfunction "VSS_2_35") (pintype "power_in"))
      (node (ref "U5") (pin "47") (pinfunction "VSS_3_47") (pintype "power_in"))
      (node (ref "U5") (pin "8") (pinfunction "VSSA_8") (pintype "power_in"))
      (node (ref "U6") (pin "4") (pinfunction "GND_4") (pintype "passive"))
      (node (ref "U7") (pin "1") (pinfunction "CLKIN_1") (pintype "passive"))
      (node (ref "U7") (pin "11") (pinfunction "FSYNC_11") (pintype "passive"))
      (node (ref "U7") (pin "15") (pinfunction "NC_15") (pintype "passive"))
      (node (ref "U7") (pin "17") (pinfunction "NC_17") (pintype "passive"))
      (node (ref "U7") (pin "18") (pinfunction "GND_18") (pintype "passive"))
      (node (ref "U8") (pin "1") (pinfunction "GND/ADJ_1") (pintype "passive"))
      (node (ref "U9") (pin "2") (pinfunction "GND_2") (pintype "passive"))
      (node (ref "USB1") (pin "13") (pinfunction "GND_13") (pintype "passive"))
      (node (ref "USB1") (pin "14") (pinfunction "GND_14") (pintype "passive"))
      (node (ref "USB1") (pin "15") (pinfunction "GND_15") (pintype "passive"))
      (node (ref "USB1") (pin "16") (pinfunction "GND_16") (pintype "passive"))
      (node (ref "USB1") (pin "A1B12") (pinfunction "GND_A1B12") (pintype "passive"))
    )
    (net (code "58") (name "Net-(C22-Pad1)") (class "Default")
      (node (ref "C22") (pin "1") (pinfunction "1_1") (pintype "passive"))
      (node (ref "R36") (pin "1") (pinfunction "1_1") (pintype "passive"))
      (node (ref "R37") (pin "2") (pinfunction "2_2") (pintype "passive"))
      (node (ref "R39") (pin "2") (pinfunction "2_2") (pintype "passive"))
    )
    (net (code "59") (name "Net-(D1-PadA)") (class "Default")
      (node (ref "D1") (pin "A") (pinfunction "A_A") (pintype "passive"))
      (node (ref "D2") (pin "A") (pinfunction "A_A") (pintype "passive"))
      (node (ref "R6") (pin "2") (pinfunction "2_2") (pintype "passive"))
    )
    (net (code "60") (name "Net-(D3-PadA)") (class "Default")
      (node (ref "D3") (pin "A") (pinfunction "A_A") (pintype "passive"))
      (node (ref "R17") (pin "2") (pinfunction "2_2") (pintype "passive"))
    )
    (net (code "61") (name "Net-(D4-K)") (class "Default")
      (node (ref "D4") (pin "2") (pinfunction "K_2") (pintype "passive"))
      (node (ref "Q2") (pin "3") (pinfunction "C_3") (pintype "passive"))
      (node (ref "R19") (pin "1") (pinfunction "1_1") (pintype "passive"))
    )
    (net (code "62") (name "Net-(D5-K)") (class "Default")
      (node (ref "D5") (pin "2") (pinfunction "K_2") (pintype "passive"))
      (node (ref "U8") (pin "3") (pinfunction "Input_3") (pintype "passive"))
      (node (ref "U9") (pin "1") (pinfunction "IN_1") (pintype "passive"))
      (node (ref "U9") (pin "3") (pinfunction "EN_3") (pintype "passive"))
    )
    (net (code "63") (name "Net-(D6-PadA)") (class "Default")
      (node (ref "D6") (pin "A") (pinfunction "A_A") (pintype "passive"))
      (node (ref "R32") (pin "2") (pinfunction "2_2") (pintype "passive"))
    )
    (net (code "64") (name "Net-(M1-EN)") (class "Default")
      (node (ref "M1") (pin "3") (pinfunction "EN_3") (pintype "passive"))
      (node (ref "R5") (pin "2") (pinfunction "2_2") (pintype "passive"))
    )
    (net (code "65") (name "Net-(M1-GPIO0)") (class "Default")
      (node (ref "M1") (pin "18") (pinfunction "GPIO0_18") (pintype "passive"))
      (node (ref "Q1") (pin "2") (pinfunction "E_2") (pintype "passive"))
      (node (ref "R10") (pin "2") (pinfunction "2_2") (pintype "passive"))
      (node (ref "R4") (pin "1") (pinfunction "1_1") (pintype "passive"))
    )
    (net (code "66") (name "Net-(M1-GPIO15)") (class "Default")
      (node (ref "M1") (pin "16") (pinfunction "GPIO15_16") (pintype "passive"))
      (node (ref "R7") (pin "1") (pinfunction "1_1") (pintype "passive"))
    )
    (net (code "67") (name "Net-(M1-RST)") (class "Default")
      (node (ref "M1") (pin "1") (pinfunction "RST_1") (pintype "passive"))
      (node (ref "R2") (pin "2") (pinfunction "2_2") (pintype "passive"))
    )
    (net (code "68") (name "Net-(P1-Pad1)") (class "Default")
      (node (ref "P1") (pin "1") (pinfunction "1_1") (pintype "passive"))
      (node (ref "S1") (pin "3") (pinfunction "3_3") (pintype "passive"))
    )
    (net (code "69") (name "Net-(Q1-B)") (class "Default")
      (node (ref "Q1") (pin "1") (pinfunction "B_1") (pintype "passive"))
      (node (ref "R9") (pin "1") (pinfunction "1_1") (pintype "passive"))
    )
    (net (code "70") (name "Net-(Q2-B)") (class "Default")
      (node (ref "Q2") (pin "1") (pinfunction "B_1") (pintype "passive"))
      (node (ref "R21") (pin "2") (pinfunction "2_2") (pintype "passive"))
    )
    (net (code "71") (name "Net-(Q2-E)") (class "Default")
      (node (ref "Q2") (pin "2") (pinfunction "E_2") (pintype "passive"))
      (node (ref "R20") (pin "1") (pinfunction "1_1") (pintype "passive"))
      (node (ref "U10") (pin "11") (pinfunction "RTS#_11") (pintype "passive"))
    )
    (net (code "72") (name "Net-(Q3-B)") (class "Default")
      (node (ref "Q3") (pin "1") (pinfunction "B_1") (pintype "passive"))
      (node (ref "R20") (pin "2") (pinfunction "2_2") (pintype "passive"))
    )
    (net (code "73") (name "Net-(Q3-C)") (class "Default")
      (node (ref "Q3") (pin "3") (pinfunction "C_3") (pintype "passive"))
      (node (ref "R22") (pin "2") (pinfunction "2_2") (pintype "passive"))
    )
    (net (code "74") (name "Net-(Q4-D)") (class "Default")
      (node (ref "Q4") (pin "3") (pinfunction "D_3") (pintype "passive"))
      (node (ref "R41") (pin "1") (pinfunction "1_1") (pintype "passive"))
    )
    (net (code "75") (name "Net-(Q4-G)") (class "Default")
      (node (ref "Q4") (pin "1") (pinfunction "G_1") (pintype "passive"))
      (node (ref "R38") (pin "2") (pinfunction "2_2") (pintype "passive"))
      (node (ref "R40") (pin "2") (pinfunction "2_2") (pintype "passive"))
    )
    (net (code "76") (name "Net-(U1-PROG)") (class "Default")
      (node (ref "R1") (pin "2") (pinfunction "2_2") (pintype "passive"))
      (node (ref "U1") (pin "2") (pinfunction "PROG_2") (pintype "passive"))
    )
    (net (code "77") (name "Net-(U1-~{CHRG})") (class "Default")
      (node (ref "D1") (pin "K") (pinfunction "K_K") (pintype "passive"))
      (node (ref "U1") (pin "7") (pinfunction "~{CHRG}_7") (pintype "passive"))
    )
    (net (code "78") (name "Net-(U1-~{STDBY})") (class "Default")
      (node (ref "D2") (pin "K") (pinfunction "K_K") (pintype "passive"))
      (node (ref "U1") (pin "6") (pinfunction "~{STDBY}_6") (pintype "passive"))
    )
    (net (code "79") (name "Net-(U4-C1)") (class "Default")
      (node (ref "C12") (pin "2") (pinfunction "2_2") (pintype "passive"))
      (node (ref "U4") (pin "10") (pinfunction "C1_10") (pintype "passive"))
    )
    (net (code "80") (name "Net-(U4-SETC)") (class "Default")
      (node (ref "C8") (pin "1") (pinfunction "1_1") (pintype "passive"))
      (node (ref "U4") (pin "12") (pinfunction "SETC_12") (pintype "passive"))
    )
    (net (code "81") (name "Net-(U4-SETP)") (class "Default")
      (node (ref "C8") (pin "2") (pinfunction "2_2") (pintype "passive"))
      (node (ref "U4") (pin "8") (pinfunction "SETP_8") (pintype "passive"))
    )
    (net (code "82") (name "Net-(U5A-PD0-OSC_IN)") (class "Default")
      (node (ref "C21") (pin "2") (pinfunction "2_2") (pintype "passive"))
      (node (ref "U5") (pin "5") (pinfunction "PD0-OSC_IN_5") (pintype "bidirectional"))
      (node (ref "Y2") (pin "2") (pinfunction "OSC2_2") (pintype "passive"))
    )
    (net (code "83") (name "Net-(U5A-PD1)") (class "Default")
      (node (ref "C20") (pin "2") (pinfunction "2_2") (pintype "passive"))
      (node (ref "U5") (pin "6") (pinfunction "PD1_6") (pintype "bidirectional"))
      (node (ref "Y2") (pin "1") (pinfunction "OSC1_1") (pintype "passive"))
    )
    (net (code "84") (name "Net-(U6-LX)") (class "Default")
      (node (ref "L1") (pin "2") (pinfunction "2_2") (pintype "passive"))
      (node (ref "U6") (pin "5") (pinfunction "LX_5") (pintype "passive"))
    )
    (net (code "85") (name "Net-(U7-AD0)") (class "Default")
      (node (ref "R23") (pin "1") (pinfunction "1_1") (pintype "passive"))
      (node (ref "U7") (pin "9") (pinfunction "AD0_9") (pintype "passive"))
    )
    (net (code "86") (name "Net-(U7-CPOUT)") (class "Default")
      (node (ref "C7") (pin "1") (pinfunction "1_1") (pintype "passive"))
      (node (ref "U7") (pin "20") (pinfunction "CPOUT_20") (pintype "passive"))
    )
    (net (code "87") (name "Net-(U7-INT)") (class "Default")
      (node (ref "R25") (pin "1") (pinfunction "1_1") (pintype "passive"))
      (node (ref "U7") (pin "12") (pinfunction "INT_12") (pintype "passive"))
    )
    (net (code "88") (name "Net-(U7-REGOUT)") (class "Default")
      (node (ref "C17") (pin "2") (pinfunction "2_2") (pintype "passive"))
      (node (ref "U7") (pin "10") (pinfunction "REGOUT_10") (pintype "passive"))
    )
    (net (code "89") (name "Net-(U10-DTR#)") (class "Default")
      (node (ref "R21") (pin "1") (pinfunction "1_1") (pintype "passive"))
      (node (ref "U10") (pin "12") (pinfunction "DTR#_12") (pintype "passive"))
    )
    (net (code "90") (name "Net-(U10-V3.3)") (class "Default")
      (node (ref "C15") (pin "1") (pinfunction "1_1") (pintype "passive"))
      (node (ref "U10") (pin "4") (pinfunction "V3.3_4") (pintype "passive"))
    )
    (net (code "91") (name "Net-(U10-XI)") (class "Default")
      (node (ref "C18") (pin "2") (pinfunction "2_2") (pintype "passive"))
      (node (ref "U10") (pin "7") (pinfunction "XI_7") (pintype "passive"))
      (node (ref "Y1") (pin "1") (pinfunction "OSC1_1") (pintype "passive"))
    )
    (net (code "92") (name "Net-(U10-XO)") (class "Default")
      (node (ref "C19") (pin "2") (pinfunction "2_2") (pintype "passive"))
      (node (ref "U10") (pin "8") (pinfunction "XO_8") (pintype "passive"))
      (node (ref "Y1") (pin "2") (pinfunction "OSC2_2") (pintype "passive"))
    )
    (net (code "93") (name "Net-(USB1-CC1)") (class "Default")
      (node (ref "R8") (pin "2") (pinfunction "2_2") (pintype "passive"))
      (node (ref "USB1") (pin "A5") (pinfunction "CC1_A5") (pintype "passive"))
    )
    (net (code "94") (name "Net-(USB1-CC2)") (class "Default")
      (node (ref "R3") (pin "2") (pinfunction "2_2") (pintype "passive"))
      (node (ref "USB1") (pin "B5") (pinfunction "CC2_B5") (pintype "passive"))
    )
    (net (code "95") (name "unconnected-(M1-ADC-Pad2)") (class "Default")
      (node (ref "M1") (pin "2") (pinfunction "ADC_2") (pintype "passive+no_connect"))
    )
    (net (code "96") (name "unconnected-(M1-CS0-Pad9)") (class "Default")
      (node (ref "M1") (pin "9") (pinfunction "CS0_9") (pintype "passive"))
    )
    (net (code "97") (name "unconnected-(M1-GPIO2-Pad17)") (class "Default")
      (node (ref "M1") (pin "17") (pinfunction "GPIO2_17") (pintype "passive+no_connect"))
    )
    (net (code "98") (name "unconnected-(M1-GPIO4-Pad19)") (class "Default")
      (node (ref "M1") (pin "19") (pinfunction "GPIO4_19") (pintype "passive+no_connect"))
    )
    (net (code "99") (name "unconnected-(M1-GPIO5-Pad20)") (class "Default")
      (node (ref "M1") (pin "20") (pinfunction "GPIO5_20") (pintype "passive+no_connect"))
    )
    (net (code "100") (name "unconnected-(M1-GPIO9-Pad11)") (class "Default")
      (node (ref "M1") (pin "11") (pinfunction "GPIO9_11") (pintype "passive"))
    )
    (net (code "101") (name "unconnected-(M1-GPIO10-Pad12)") (class "Default")
      (node (ref "M1") (pin "12") (pinfunction "GPIO10_12") (pintype "passive"))
    )
    (net (code "102") (name "unconnected-(M1-GPIO12-Pad6)") (class "Default")
      (node (ref "M1") (pin "6") (pinfunction "GPIO12_6") (pintype "passive+no_connect"))
    )
    (net (code "103") (name "unconnected-(M1-GPIO13-Pad7)") (class "Default")
      (node (ref "M1") (pin "7") (pinfunction "GPIO13_7") (pintype "passive+no_connect"))
    )
    (net (code "104") (name "unconnected-(M1-GPIO14-Pad5)") (class "Default")
      (node (ref "M1") (pin "5") (pinfunction "GPIO14_5") (pintype "passive+no_connect"))
    )
    (net (code "105") (name "unconnected-(M1-GPIO16-Pad4)") (class "Default")
      (node (ref "M1") (pin "4") (pinfunction "GPIO16_4") (pintype "passive+no_connect"))
    )
    (net (code "106") (name "unconnected-(M1-MISO-Pad10)") (class "Default")
      (node (ref "M1") (pin "10") (pinfunction "MISO_10") (pintype "passive"))
    )
    (net (code "107") (name "unconnected-(M1-MOSI-Pad13)") (class "Default")
      (node (ref "M1") (pin "13") (pinfunction "MOSI_13") (pintype "passive"))
    )
    (net (code "108") (name "unconnected-(M1-SCLK-Pad14)") (class "Default")
      (node (ref "M1") (pin "14") (pinfunction "SCLK_14") (pintype "passive"))
    )
    (net (code "109") (name "unconnected-(M1-VCC-Pad8)") (class "Default")
      (node (ref "M1") (pin "8") (pinfunction "VCC_8") (pintype "passive+no_connect"))
    )
    (net (code "110") (name "unconnected-(P2-Pad8)") (class "Default")
      (node (ref "P2") (pin "8") (pinfunction "8_8") (pintype "passive"))
    )
    (net (code "111") (name "unconnected-(P2-Pad10)") (class "Default")
      (node (ref "P2") (pin "10") (pinfunction "10_10") (pintype "passive"))
    )
    (net (code "112") (name "unconnected-(U3-SDO-Pad6)") (class "Default")
      (node (ref "U3") (pin "6") (pinfunction "SDO_6") (pintype "passive+no_connect"))
    )
    (net (code "113") (name "unconnected-(U4-I2C{slash}SPI-Pad6)") (class "Default")
      (node (ref "U4") (pin "6") (pinfunction "I2C/SPI_6") (pintype "passive+no_connect"))
    )
    (net (code "114") (name "unconnected-(U4-NC-Pad3)") (class "Default")
      (node (ref "U4") (pin "3") (pinfunction "NC_3") (pintype "passive+no_connect"))
    )
    (net (code "115") (name "unconnected-(U4-NC-Pad5)") (class "Default")
      (node (ref "U4") (pin "5") (pinfunction "NC_5") (pintype "passive+no_connect"))
    )
    (net (code "116") (name "unconnected-(U4-NC-Pad7)") (class "Default")
      (node (ref "U4") (pin "7") (pinfunction "NC_7") (pintype "passive+no_connect"))
    )
    (net (code "117") (name "unconnected-(U4-NC-Pad14)") (class "Default")
      (node (ref "U4") (pin "14") (pinfunction "NC_14") (pintype "passive+no_connect"))
    )
    (net (code "118") (name "unconnected-(U4-S1-Pad4)") (class "Default")
      (node (ref "U4") (pin "4") (pinfunction "S1_4") (pintype "passive+no_connect"))
    )
    (net (code "119") (name "unconnected-(U6-NC-Pad3)") (class "Default")
      (node (ref "U6") (pin "3") (pinfunction "NC_3") (pintype "passive+no_connect"))
    )
    (net (code "120") (name "unconnected-(U7-NC-Pad2)") (class "Default")
      (node (ref "U7") (pin "2") (pinfunction "NC_2") (pintype "passive+no_connect"))
    )
    (net (code "121") (name "unconnected-(U7-NC-Pad3)") (class "Default")
      (node (ref "U7") (pin "3") (pinfunction "NC_3") (pintype "passive+no_connect"))
    )
    (net (code "122") (name "unconnected-(U7-NC-Pad4)") (class "Default")
      (node (ref "U7") (pin "4") (pinfunction "NC_4") (pintype "passive+no_connect"))
    )
    (net (code "123") (name "unconnected-(U7-NC-Pad5)") (class "Default")
      (node (ref "U7") (pin "5") (pinfunction "NC_5") (pintype "passive+no_connect"))
    )
    (net (code "124") (name "unconnected-(U7-NC-Pad14)") (class "Default")
      (node (ref "U7") (pin "14") (pinfunction "NC_14") (pintype "passive"))
    )
    (net (code "125") (name "unconnected-(U7-NC-Pad16)") (class "Default")
      (node (ref "U7") (pin "16") (pinfunction "NC_16") (pintype "passive+no_connect"))
    )
    (net (code "126") (name "unconnected-(U7-RESV-Pad19)") (class "Default")
      (node (ref "U7") (pin "19") (pinfunction "RESV_19") (pintype "passive+no_connect"))
    )
    (net (code "127") (name "unconnected-(U7-RESV-Pad21)") (class "Default")
      (node (ref "U7") (pin "21") (pinfunction "RESV_21") (pintype "passive+no_connect"))
    )
    (net (code "128") (name "unconnected-(U7-RESV-Pad22)") (class "Default")
      (node (ref "U7") (pin "22") (pinfunction "RESV_22") (pintype "passive+no_connect"))
    )
    (net (code "129") (name "unconnected-(U8-Output-Pad4)") (class "Default")
      (node (ref "U8") (pin "4") (pinfunction "Output_4") (pintype "passive+no_connect"))
    )
    (net (code "130") (name "unconnected-(U9-BYP-Pad4)") (class "Default")
      (node (ref "U9") (pin "4") (pinfunction "BYP_4") (pintype "passive+no_connect"))
    )
    (net (code "131") (name "unconnected-(U10-CTS#-Pad9)") (class "Default")
      (node (ref "U10") (pin "9") (pinfunction "CTS#_9") (pintype "passive"))
    )
    (net (code "132") (name "unconnected-(U10-DCD#-Pad13)") (class "Default")
      (node (ref "U10") (pin "13") (pinfunction "DCD#_13") (pintype "passive"))
    )
    (net (code "133") (name "unconnected-(U10-DSR#-Pad15)") (class "Default")
      (node (ref "U10") (pin "15") (pinfunction "DSR#_15") (pintype "passive"))
    )
    (net (code "134") (name "unconnected-(U10-R232-Pad10)") (class "Default")
      (node (ref "U10") (pin "10") (pinfunction "R232_10") (pintype "passive"))
    )
    (net (code "135") (name "unconnected-(U10-RI#-Pad14)") (class "Default")
      (node (ref "U10") (pin "14") (pinfunction "RI#_14") (pintype "passive"))
    )
    (net (code "136") (name "unconnected-(USB1-GND-PadB1A12)") (class "Default")
      (node (ref "USB1") (pin "B1A12") (pinfunction "GND_B1A12") (pintype "passive"))
    )
    (net (code "137") (name "unconnected-(USB1-SBU1-PadA8)") (class "Default")
      (node (ref "USB1") (pin "A8") (pinfunction "SBU1_A8") (pintype "passive+no_connect"))
    )
    (net (code "138") (name "unconnected-(USB1-SBU2-PadB8)") (class "Default")
      (node (ref "USB1") (pin "B8") (pinfunction "SBU2_B8") (pintype "passive+no_connect"))
    )
  )
)
